# MesschieberV4.net
KiCad netlist of a schematic drawn in EAGLE
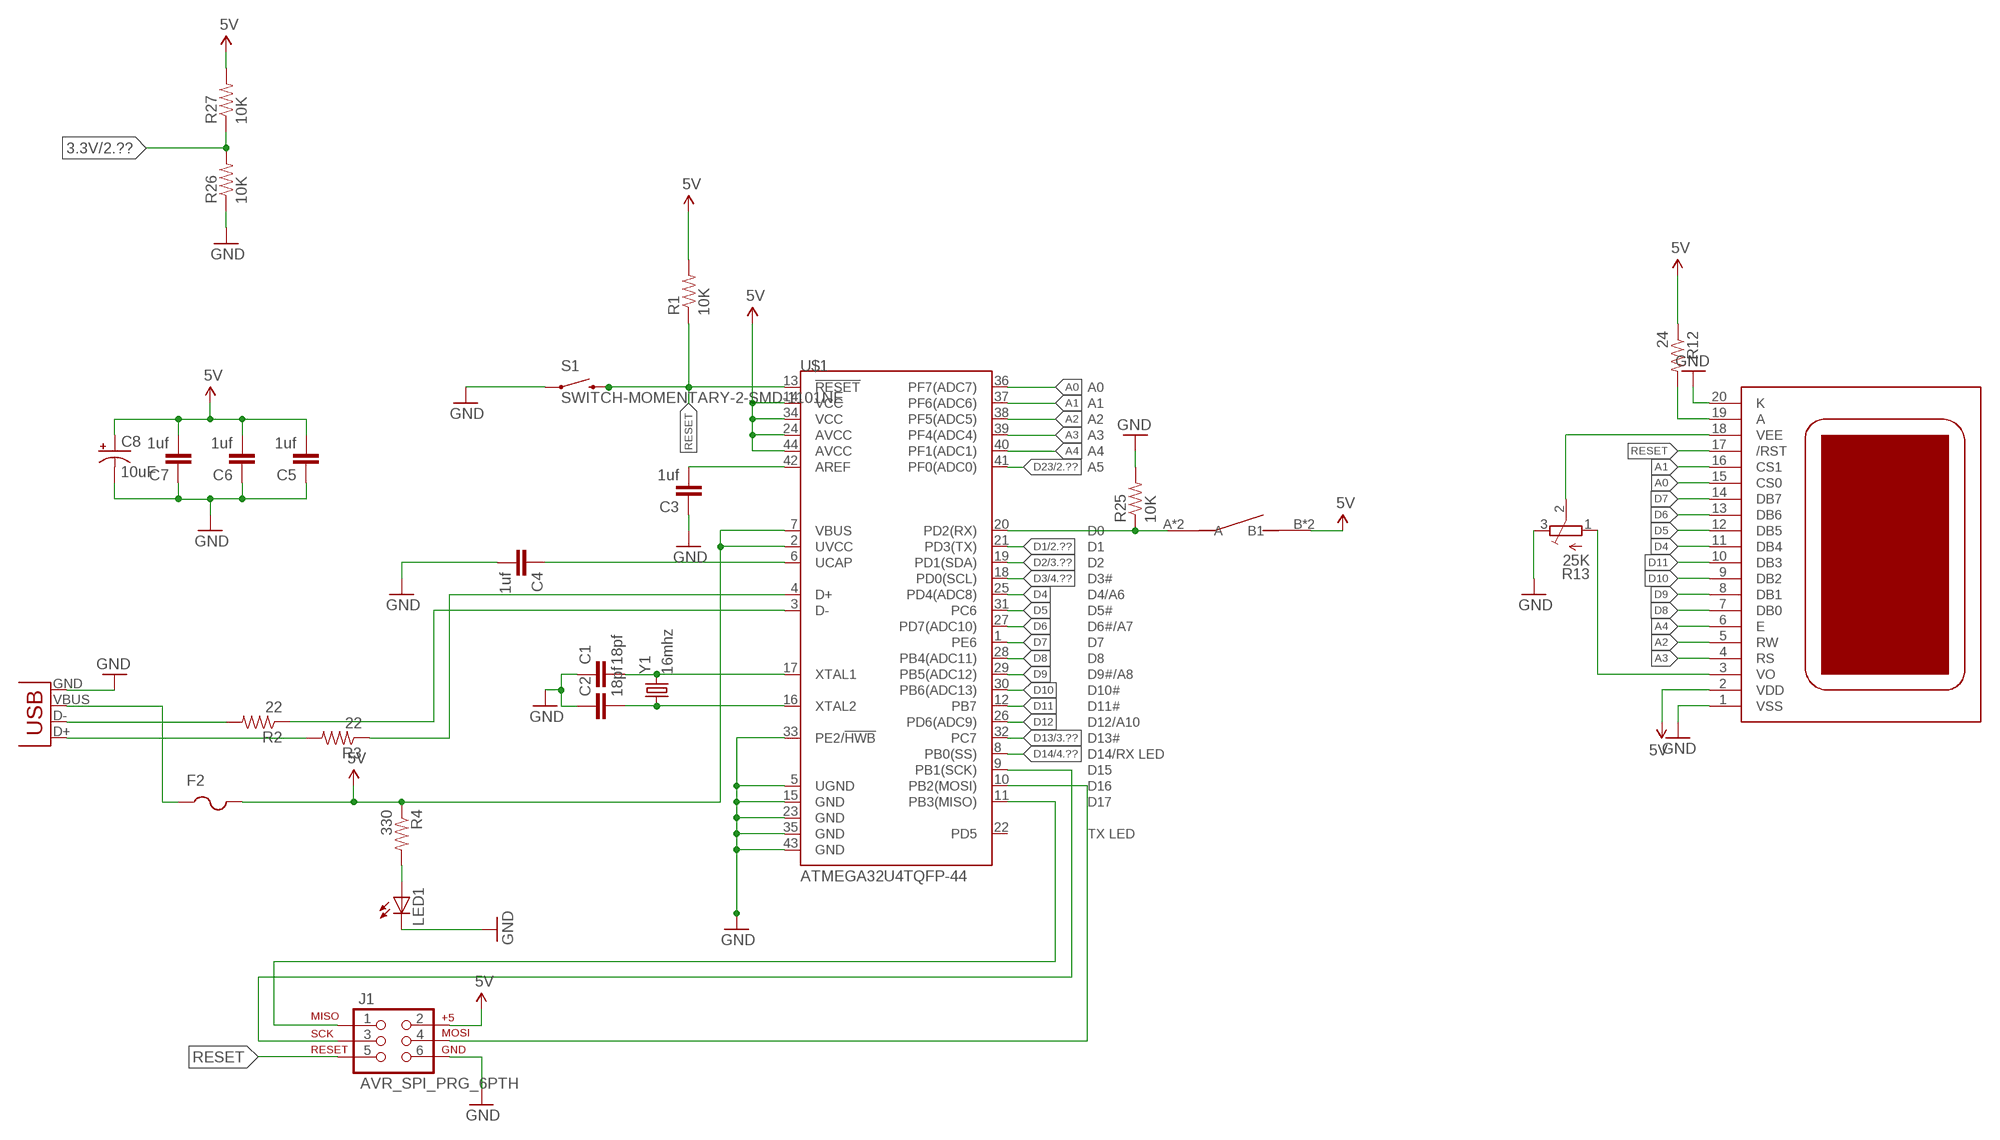
[diagram p0: schematic, sheet 1]
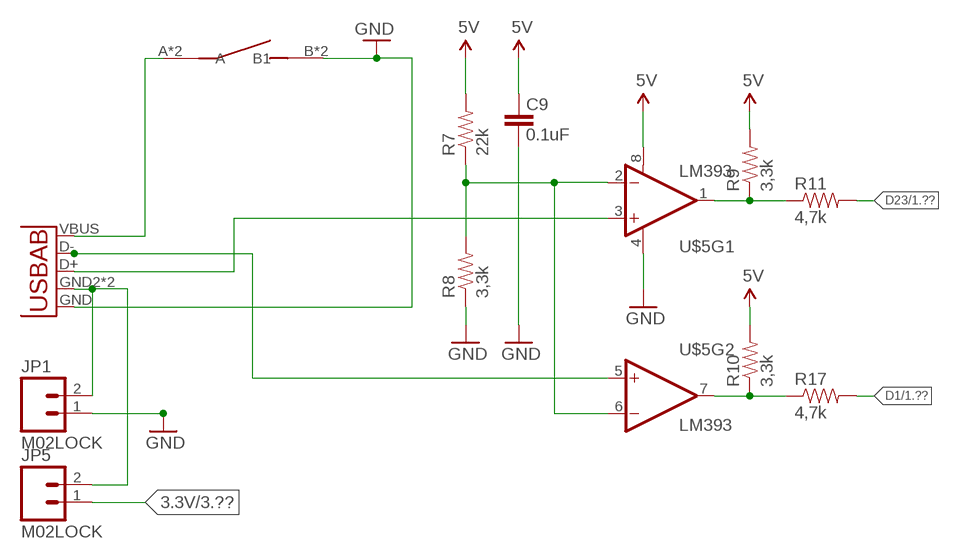
[diagram p1: schematic, sheet 2]
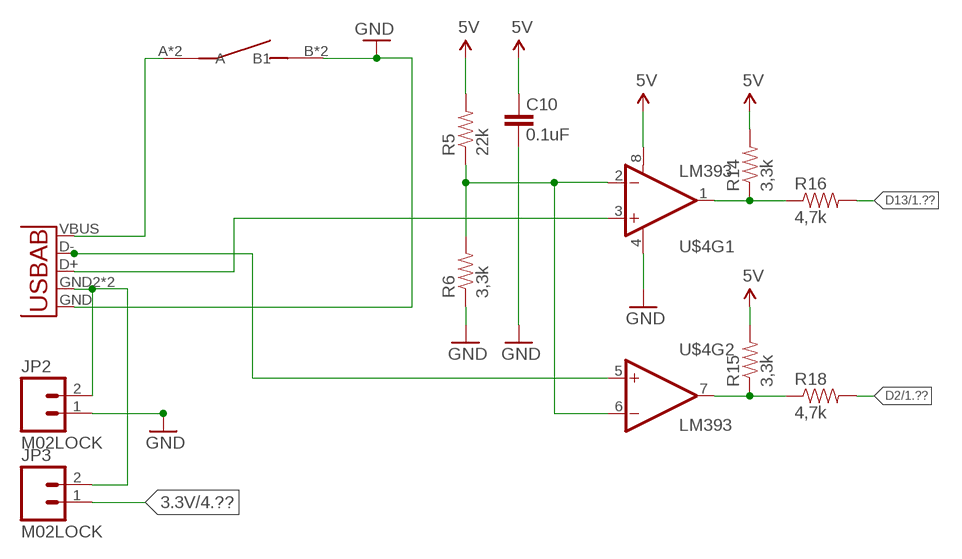
[diagram p2: schematic, sheet 3]
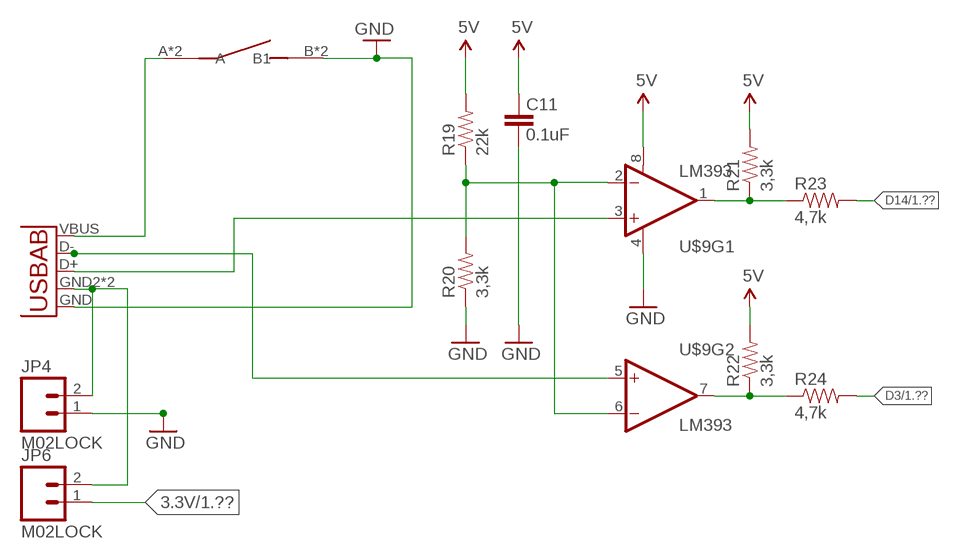
[diagram p3: schematic, sheet 4]

(export (version "E")
  (design (tool "Eeschema 10.0.6"))
  (components
    (comp (ref "C11")
      (value "0.1uF")
      (footprint "eagle-import:0805")
      (libsource (lib "eagle-import") (part "CAP0805"))
    )
    (comp (ref "JP4")
      (value "M02LOCK")
      (footprint "eagle-import:1X02_LOCK")
      (libsource (lib "eagle-import") (part "M02LOCK"))
    )
    (comp (ref "JP6")
      (value "M02LOCK")
      (footprint "eagle-import:1X02_LOCK")
      (libsource (lib "eagle-import") (part "M02LOCK"))
    )
    (comp (ref "R19")
      (value "22k")
      (footprint "eagle-import:0805")
      (libsource (lib "eagle-import") (part "RESISTOR"))
    )
    (comp (ref "R20")
      (value "3,3k")
      (footprint "eagle-import:0805")
      (libsource (lib "eagle-import") (part "RESISTOR"))
    )
    (comp (ref "R21")
      (value "3,3k")
      (footprint "eagle-import:0805")
      (libsource (lib "eagle-import") (part "RESISTOR"))
    )
    (comp (ref "R22")
      (value "3,3k")
      (footprint "eagle-import:0805")
      (libsource (lib "eagle-import") (part "RESISTOR"))
    )
    (comp (ref "R23")
      (value "4,7k")
      (footprint "eagle-import:0805")
      (libsource (lib "eagle-import") (part "RESISTOR"))
    )
    (comp (ref "R24")
      (value "4,7k")
      (footprint "eagle-import:0805")
      (libsource (lib "eagle-import") (part "RESISTOR"))
    )
    (comp (ref "U$9")
      (value "LM393")
      (footprint "eagle-import:SO08")
      (libsource (lib "eagle-import") (part "LM393"))
    )
    (comp (ref "U$10")
      (value "USB-A")
      (footprint "eagle-import:USB-A")
      (libsource (lib "eagle-import") (part "USB-A"))
    )
    (comp (ref "U$11")
      (value "TASTE_R3FTL6")
      (footprint "eagle-import:TASTE_R3FTL6")
      (libsource (lib "eagle-import") (part "TASTE_R3FTL6"))
    )
    (comp (ref "C10")
      (value "0.1uF")
      (footprint "eagle-import:0805")
      (libsource (lib "eagle-import") (part "CAP0805"))
    )
    (comp (ref "JP2")
      (value "M02LOCK")
      (footprint "eagle-import:1X02_LOCK")
      (libsource (lib "eagle-import") (part "M02LOCK"))
    )
    (comp (ref "JP3")
      (value "M02LOCK")
      (footprint "eagle-import:1X02_LOCK")
      (libsource (lib "eagle-import") (part "M02LOCK"))
    )
    (comp (ref "R5")
      (value "22k")
      (footprint "eagle-import:0805")
      (libsource (lib "eagle-import") (part "RESISTOR"))
    )
    (comp (ref "R6")
      (value "3,3k")
      (footprint "eagle-import:0805")
      (libsource (lib "eagle-import") (part "RESISTOR"))
    )
    (comp (ref "R14")
      (value "3,3k")
      (footprint "eagle-import:0805")
      (libsource (lib "eagle-import") (part "RESISTOR"))
    )
    (comp (ref "R15")
      (value "3,3k")
      (footprint "eagle-import:0805")
      (libsource (lib "eagle-import") (part "RESISTOR"))
    )
    (comp (ref "R16")
      (value "4,7k")
      (footprint "eagle-import:0805")
      (libsource (lib "eagle-import") (part "RESISTOR"))
    )
    (comp (ref "R18")
      (value "4,7k")
      (footprint "eagle-import:0805")
      (libsource (lib "eagle-import") (part "RESISTOR"))
    )
    (comp (ref "U$4")
      (value "LM393")
      (footprint "eagle-import:SO08")
      (libsource (lib "eagle-import") (part "LM393"))
    )
    (comp (ref "U$6")
      (value "USB-A")
      (footprint "eagle-import:USB-A")
      (libsource (lib "eagle-import") (part "USB-A"))
    )
    (comp (ref "U$8")
      (value "TASTE_R3FTL6")
      (footprint "eagle-import:TASTE_R3FTL6")
      (libsource (lib "eagle-import") (part "TASTE_R3FTL6"))
    )
    (comp (ref "C9")
      (value "0.1uF")
      (footprint "eagle-import:0805")
      (libsource (lib "eagle-import") (part "CAP0805"))
    )
    (comp (ref "JP1")
      (value "M02LOCK")
      (footprint "eagle-import:1X02_LOCK")
      (libsource (lib "eagle-import") (part "M02LOCK"))
    )
    (comp (ref "JP5")
      (value "M02LOCK")
      (footprint "eagle-import:1X02_LOCK")
      (libsource (lib "eagle-import") (part "M02LOCK"))
    )
    (comp (ref "R7")
      (value "22k")
      (footprint "eagle-import:0805")
      (libsource (lib "eagle-import") (part "RESISTOR"))
    )
    (comp (ref "R8")
      (value "3,3k")
      (footprint "eagle-import:0805")
      (libsource (lib "eagle-import") (part "RESISTOR"))
    )
    (comp (ref "R9")
      (value "3,3k")
      (footprint "eagle-import:0805")
      (libsource (lib "eagle-import") (part "RESISTOR"))
    )
    (comp (ref "R10")
      (value "3,3k")
      (footprint "eagle-import:0805")
      (libsource (lib "eagle-import") (part "RESISTOR"))
    )
    (comp (ref "R11")
      (value "4,7k")
      (footprint "eagle-import:0805")
      (libsource (lib "eagle-import") (part "RESISTOR"))
    )
    (comp (ref "R17")
      (value "4,7k")
      (footprint "eagle-import:0805")
      (libsource (lib "eagle-import") (part "RESISTOR"))
    )
    (comp (ref "U$3")
      (value "TASTE_R3FTL6")
      (footprint "eagle-import:TASTE_R3FTL6")
      (libsource (lib "eagle-import") (part "TASTE_R3FTL6"))
    )
    (comp (ref "U$5")
      (value "LM393")
      (footprint "eagle-import:SO08")
      (libsource (lib "eagle-import") (part "LM393"))
    )
    (comp (ref "U$7")
      (value "USB-A")
      (footprint "eagle-import:USB-A")
      (libsource (lib "eagle-import") (part "USB-A"))
    )
    (comp (ref "C1")
      (value "18pf")
      (footprint "eagle-import:0805")
      (libsource (lib "eagle-import") (part "SparkFun-Capacitors_CAP0805"))
    )
    (comp (ref "C2")
      (value "18pf")
      (footprint "eagle-import:0805")
      (libsource (lib "eagle-import") (part "SparkFun-Capacitors_CAP0805"))
    )
    (comp (ref "C3")
      (value "1uf")
      (footprint "eagle-import:0805")
      (libsource (lib "eagle-import") (part "SparkFun-Capacitors_CAP0805"))
    )
    (comp (ref "C4")
      (value "1uf")
      (footprint "eagle-import:0805")
      (libsource (lib "eagle-import") (part "SparkFun-Capacitors_CAP0805"))
    )
    (comp (ref "C5")
      (value "1uf")
      (footprint "eagle-import:0805")
      (libsource (lib "eagle-import") (part "SparkFun-Capacitors_CAP0805"))
    )
    (comp (ref "C6")
      (value "1uf")
      (footprint "eagle-import:0805")
      (libsource (lib "eagle-import") (part "SparkFun-Capacitors_CAP0805"))
    )
    (comp (ref "C7")
      (value "1uf")
      (footprint "eagle-import:0805")
      (libsource (lib "eagle-import") (part "SparkFun-Capacitors_CAP0805"))
    )
    (comp (ref "C8")
      (value "10uF")
      (footprint "eagle-import:EIA3528")
      (libsource (lib "eagle-import") (part "10UF-20V-10%(TANT)"))
    )
    (comp (ref "F2")
      (value "PTCFUSE-1812")
      (footprint "eagle-import:1812")
      (libsource (lib "eagle-import") (part "PTCFUSE-1812"))
    )
    (comp (ref "J1")
      (value "AVR_SPI_PRG_6PTH")
      (footprint "eagle-import:2X3")
      (libsource (lib "eagle-import") (part "AVR_SPI_PRG_6PTH"))
    )
    (comp (ref "JP7")
      (value "USB-SMD-NS")
      (footprint "eagle-import:USB-MINIB-NOSTOP")
      (libsource (lib "eagle-import") (part "USB-SMD-NS"))
    )
    (comp (ref "LED1")
      (value "LEDSML0805")
      (footprint "eagle-import:SML0805")
      (libsource (lib "eagle-import") (part "LEDSML0805"))
    )
    (comp (ref "R1")
      (value "10K")
      (footprint "eagle-import:0805")
      (libsource (lib "eagle-import") (part "RESISTOR"))
    )
    (comp (ref "R2")
      (value "22")
      (footprint "eagle-import:0805")
      (libsource (lib "eagle-import") (part "RESISTOR"))
    )
    (comp (ref "R3")
      (value "22")
      (footprint "eagle-import:0805")
      (libsource (lib "eagle-import") (part "RESISTOR"))
    )
    (comp (ref "R4")
      (value "330")
      (footprint "eagle-import:0805")
      (libsource (lib "eagle-import") (part "RESISTOR"))
    )
    (comp (ref "R12")
      (value "24")
      (footprint "eagle-import:0805")
      (libsource (lib "eagle-import") (part "RESISTOR"))
    )
    (comp (ref "R13")
      (value "25K")
      (footprint "eagle-import:SM-42_43A")
      (libsource (lib "eagle-import") (part "TRIM_EU-SM-42/43A"))
    )
    (comp (ref "R25")
      (value "10K")
      (footprint "eagle-import:0805")
      (libsource (lib "eagle-import") (part "RESISTOR"))
    )
    (comp (ref "R26")
      (value "10K")
      (footprint "eagle-import:0805")
      (libsource (lib "eagle-import") (part "RESISTOR"))
    )
    (comp (ref "R27")
      (value "10K")
      (footprint "eagle-import:0805")
      (libsource (lib "eagle-import") (part "RESISTOR"))
    )
    (comp (ref "S1")
      (value "SWITCH-MOMENTARY-2-SMD-1101NE")
      (footprint "eagle-import:TACTILE-SWITCH-1101NE")
      (libsource (lib "eagle-import") (part "SWITCH-MOMENTARY-2-SMD-1101NE"))
    )
    (comp (ref "U$1")
      (value "ATMEGA32U4TQFP-44")
      (footprint "eagle-import:TQFP44")
      (libsource (lib "eagle-import") (part "ATMEGA32U4TQFP-44"))
    )
    (comp (ref "U$2")
      (value "TS12864A")
      (footprint "eagle-import:TS12864")
      (libsource (lib "eagle-import") (part "TS12864A"))
    )
    (comp (ref "U$12")
      (value "TASTE_R3FTL6")
      (footprint "eagle-import:TASTE_R3FTL6")
      (libsource (lib "eagle-import") (part "TASTE_R3FTL6"))
    )
    (comp (ref "Y1")
      (value "16mhz")
      (footprint "eagle-import:CRYSTAL-SMD-5X3")
      (libsource (lib "eagle-import") (part "CRYSTAL5X3"))
    )
  )
  (nets
    (net (code "1") (name "3.3V") (class "Default")
      (node (ref "JP3") (pin "1") (pinfunction "1_1") (pintype "passive"))
      (node (ref "JP5") (pin "1") (pinfunction "1_1") (pintype "passive"))
      (node (ref "JP6") (pin "1") (pinfunction "1_1") (pintype "passive"))
      (node (ref "R26") (pin "2") (pinfunction "2_2") (pintype "passive"))
      (node (ref "R27") (pin "1") (pinfunction "1_1") (pintype "passive"))
    )
    (net (code "2") (name "5V") (class "Default")
      (node (ref "C10") (pin "2") (pinfunction "2_2") (pintype "passive"))
      (node (ref "C11") (pin "2") (pinfunction "2_2") (pintype "passive"))
      (node (ref "C5") (pin "2") (pinfunction "2_2") (pintype "passive"))
      (node (ref "C6") (pin "2") (pinfunction "2_2") (pintype "passive"))
      (node (ref "C7") (pin "2") (pinfunction "2_2") (pintype "passive"))
      (node (ref "C8") (pin "A") (pinfunction "+_A") (pintype "passive"))
      (node (ref "C9") (pin "2") (pinfunction "2_2") (pintype "passive"))
      (node (ref "F2") (pin "2") (pinfunction "2_2") (pintype "passive"))
      (node (ref "J1") (pin "2") (pinfunction "2_2") (pintype "passive"))
      (node (ref "R1") (pin "2") (pinfunction "2_2") (pintype "passive"))
      (node (ref "R10") (pin "2") (pinfunction "2_2") (pintype "passive"))
      (node (ref "R12") (pin "1") (pinfunction "1_1") (pintype "passive"))
      (node (ref "R14") (pin "2") (pinfunction "2_2") (pintype "passive"))
      (node (ref "R15") (pin "2") (pinfunction "2_2") (pintype "passive"))
      (node (ref "R19") (pin "2") (pinfunction "2_2") (pintype "passive"))
      (node (ref "R21") (pin "2") (pinfunction "2_2") (pintype "passive"))
      (node (ref "R22") (pin "2") (pinfunction "2_2") (pintype "passive"))
      (node (ref "R27") (pin "2") (pinfunction "2_2") (pintype "passive"))
      (node (ref "R4") (pin "1") (pinfunction "1_1") (pintype "passive"))
      (node (ref "R5") (pin "2") (pinfunction "2_2") (pintype "passive"))
      (node (ref "R7") (pin "2") (pinfunction "2_2") (pintype "passive"))
      (node (ref "R9") (pin "2") (pinfunction "2_2") (pintype "passive"))
      (node (ref "U$1") (pin "14") (pinfunction "VCC_14") (pintype "bidirectional"))
      (node (ref "U$1") (pin "2") (pinfunction "UVCC_2") (pintype "bidirectional"))
      (node (ref "U$1") (pin "24") (pinfunction "AVCC_24") (pintype "bidirectional"))
      (node (ref "U$1") (pin "34") (pinfunction "VCC_34") (pintype "bidirectional"))
      (node (ref "U$1") (pin "44") (pinfunction "AVCC_44") (pintype "bidirectional"))
      (node (ref "U$1") (pin "7") (pinfunction "VBUS_7") (pintype "bidirectional"))
      (node (ref "U$12") (pin "B") (pinfunction "B1_B") (pintype "bidirectional"))
      (node (ref "U$12") (pin "B1") (pinfunction "B1_B1") (pintype "bidirectional"))
      (node (ref "U$2") (pin "2") (pinfunction "VDD_2") (pintype "power_in"))
      (node (ref "U$4") (pin "8") (pinfunction "V+_8") (pintype "power_in"))
      (node (ref "U$5") (pin "8") (pinfunction "V+_8") (pintype "power_in"))
      (node (ref "U$9") (pin "8") (pinfunction "V+_8") (pintype "power_in"))
    )
    (net (code "3") (name "A0") (class "Default")
      (node (ref "U$1") (pin "36") (pinfunction "PF7(ADC7)_36") (pintype "bidirectional"))
      (node (ref "U$2") (pin "15") (pinfunction "CS0_15") (pintype "input"))
    )
    (net (code "4") (name "A1") (class "Default")
      (node (ref "U$1") (pin "37") (pinfunction "PF6(ADC6)_37") (pintype "bidirectional"))
      (node (ref "U$2") (pin "16") (pinfunction "CS1_16") (pintype "input"))
    )
    (net (code "5") (name "A2") (class "Default")
      (node (ref "U$1") (pin "38") (pinfunction "PF5(ADC5)_38") (pintype "bidirectional"))
      (node (ref "U$2") (pin "5") (pinfunction "RW_5") (pintype "input"))
    )
    (net (code "6") (name "A3") (class "Default")
      (node (ref "U$1") (pin "39") (pinfunction "PF4(ADC4)_39") (pintype "bidirectional"))
      (node (ref "U$2") (pin "4") (pinfunction "RS_4") (pintype "input"))
    )
    (net (code "7") (name "A4") (class "Default")
      (node (ref "U$1") (pin "40") (pinfunction "PF1(ADC1)_40") (pintype "bidirectional"))
      (node (ref "U$2") (pin "6") (pinfunction "E_6") (pintype "input"))
    )
    (net (code "8") (name "D1") (class "Default")
      (node (ref "R17") (pin "2") (pinfunction "2_2") (pintype "passive"))
      (node (ref "U$1") (pin "21") (pinfunction "PD3(TX)_21") (pintype "bidirectional"))
    )
    (net (code "9") (name "D2") (class "Default")
      (node (ref "R18") (pin "2") (pinfunction "2_2") (pintype "passive"))
      (node (ref "U$1") (pin "19") (pinfunction "PD1(SDA)_19") (pintype "bidirectional"))
    )
    (net (code "10") (name "D3") (class "Default")
      (node (ref "R24") (pin "2") (pinfunction "2_2") (pintype "passive"))
      (node (ref "U$1") (pin "18") (pinfunction "PD0(SCL)_18") (pintype "bidirectional"))
    )
    (net (code "11") (name "D4") (class "Default")
      (node (ref "U$1") (pin "25") (pinfunction "PD4(ADC8)_25") (pintype "bidirectional"))
      (node (ref "U$2") (pin "11") (pinfunction "DB4_11") (pintype "bidirectional"))
    )
    (net (code "12") (name "D5") (class "Default")
      (node (ref "U$1") (pin "31") (pinfunction "PC6_31") (pintype "bidirectional"))
      (node (ref "U$2") (pin "12") (pinfunction "DB5_12") (pintype "bidirectional"))
    )
    (net (code "13") (name "D6") (class "Default")
      (node (ref "U$1") (pin "27") (pinfunction "PD7(ADC10)_27") (pintype "bidirectional"))
      (node (ref "U$2") (pin "13") (pinfunction "DB6_13") (pintype "bidirectional"))
    )
    (net (code "14") (name "D7") (class "Default")
      (node (ref "U$1") (pin "1") (pinfunction "PE6_1") (pintype "bidirectional"))
      (node (ref "U$2") (pin "14") (pinfunction "DB7_14") (pintype "bidirectional"))
    )
    (net (code "15") (name "D8") (class "Default")
      (node (ref "U$1") (pin "28") (pinfunction "PB4(ADC11)_28") (pintype "bidirectional"))
      (node (ref "U$2") (pin "7") (pinfunction "DB0_7") (pintype "bidirectional"))
    )
    (net (code "16") (name "D9") (class "Default")
      (node (ref "U$1") (pin "29") (pinfunction "PB5(ADC12)_29") (pintype "bidirectional"))
      (node (ref "U$2") (pin "8") (pinfunction "DB1_8") (pintype "bidirectional"))
    )
    (net (code "17") (name "D10") (class "Default")
      (node (ref "U$1") (pin "30") (pinfunction "PB6(ADC13)_30") (pintype "bidirectional"))
      (node (ref "U$2") (pin "9") (pinfunction "DB2_9") (pintype "bidirectional"))
    )
    (net (code "18") (name "D11") (class "Default")
      (node (ref "U$1") (pin "12") (pinfunction "PB7_12") (pintype "bidirectional"))
      (node (ref "U$2") (pin "10") (pinfunction "DB3_10") (pintype "bidirectional"))
    )
    (net (code "19") (name "D12") (class "Default")
      (node (ref "U$1") (pin "26") (pinfunction "PD6(ADC9)_26") (pintype "bidirectional"))
    )
    (net (code "20") (name "D13") (class "Default")
      (node (ref "R16") (pin "2") (pinfunction "2_2") (pintype "passive"))
      (node (ref "U$1") (pin "32") (pinfunction "PC7_32") (pintype "bidirectional"))
    )
    (net (code "21") (name "D14") (class "Default")
      (node (ref "R23") (pin "2") (pinfunction "2_2") (pintype "passive"))
      (node (ref "U$1") (pin "8") (pinfunction "PB0(SS)_8") (pintype "bidirectional"))
    )
    (net (code "22") (name "D23") (class "Default")
      (node (ref "R11") (pin "2") (pinfunction "2_2") (pintype "passive"))
      (node (ref "U$1") (pin "41") (pinfunction "PF0(ADC0)_41") (pintype "bidirectional"))
    )
    (net (code "23") (name "GND") (class "Default")
      (node (ref "C1") (pin "1") (pinfunction "1_1") (pintype "passive"))
      (node (ref "C10") (pin "1") (pinfunction "1_1") (pintype "passive"))
      (node (ref "C11") (pin "1") (pinfunction "1_1") (pintype "passive"))
      (node (ref "C2") (pin "1") (pinfunction "1_1") (pintype "passive"))
      (node (ref "C3") (pin "1") (pinfunction "1_1") (pintype "passive"))
      (node (ref "C4") (pin "2") (pinfunction "2_2") (pintype "passive"))
      (node (ref "C5") (pin "1") (pinfunction "1_1") (pintype "passive"))
      (node (ref "C6") (pin "1") (pinfunction "1_1") (pintype "passive"))
      (node (ref "C7") (pin "1") (pinfunction "1_1") (pintype "passive"))
      (node (ref "C8") (pin "C") (pinfunction "-_C") (pintype "passive"))
      (node (ref "C9") (pin "1") (pinfunction "1_1") (pintype "passive"))
      (node (ref "J1") (pin "6") (pinfunction "6_6") (pintype "passive"))
      (node (ref "JP1") (pin "1") (pinfunction "1_1") (pintype "passive"))
      (node (ref "JP2") (pin "1") (pinfunction "1_1") (pintype "passive"))
      (node (ref "JP4") (pin "1") (pinfunction "1_1") (pintype "passive"))
      (node (ref "JP7") (pin "GND") (pinfunction "GND_GND") (pintype "bidirectional"))
      (node (ref "LED1") (pin "C") (pinfunction "C_C") (pintype "passive"))
      (node (ref "R13") (pin "3") (pinfunction "E_3") (pintype "passive"))
      (node (ref "R20") (pin "1") (pinfunction "1_1") (pintype "passive"))
      (node (ref "R25") (pin "2") (pinfunction "2_2") (pintype "passive"))
      (node (ref "R26") (pin "1") (pinfunction "1_1") (pintype "passive"))
      (node (ref "R6") (pin "1") (pinfunction "1_1") (pintype "passive"))
      (node (ref "R8") (pin "1") (pinfunction "1_1") (pintype "passive"))
      (node (ref "S1") (pin "P$1") (pinfunction "1_P$1") (pintype "passive"))
      (node (ref "U$1") (pin "15") (pinfunction "GND_15") (pintype "bidirectional"))
      (node (ref "U$1") (pin "23") (pinfunction "GND_23") (pintype "bidirectional"))
      (node (ref "U$1") (pin "33") (pinfunction "PE2/~{HWB}_33") (pintype "bidirectional"))
      (node (ref "U$1") (pin "35") (pinfunction "GND_35") (pintype "bidirectional"))
      (node (ref "U$1") (pin "43") (pinfunction "GND_43") (pintype "bidirectional"))
      (node (ref "U$1") (pin "5") (pinfunction "UGND_5") (pintype "bidirectional"))
      (node (ref "U$10") (pin "GND") (pinfunction "GND_GND") (pintype "bidirectional"))
      (node (ref "U$11") (pin "B") (pinfunction "B1_B") (pintype "bidirectional"))
      (node (ref "U$11") (pin "B1") (pinfunction "B1_B1") (pintype "bidirectional"))
      (node (ref "U$2") (pin "1") (pinfunction "VSS_1") (pintype "power_in"))
      (node (ref "U$2") (pin "20") (pinfunction "K_20") (pintype "input"))
      (node (ref "U$3") (pin "B") (pinfunction "B1_B") (pintype "bidirectional"))
      (node (ref "U$3") (pin "B1") (pinfunction "B1_B1") (pintype "bidirectional"))
      (node (ref "U$4") (pin "4") (pinfunction "V-_4") (pintype "power_in"))
      (node (ref "U$5") (pin "4") (pinfunction "V-_4") (pintype "power_in"))
      (node (ref "U$6") (pin "GND") (pinfunction "GND_GND") (pintype "bidirectional"))
      (node (ref "U$7") (pin "GND") (pinfunction "GND_GND") (pintype "bidirectional"))
      (node (ref "U$8") (pin "B") (pinfunction "B1_B") (pintype "bidirectional"))
      (node (ref "U$8") (pin "B1") (pinfunction "B1_B1") (pintype "bidirectional"))
      (node (ref "U$9") (pin "4") (pinfunction "V-_4") (pintype "power_in"))
    )
    (net (code "24") (name "Net-(F2-Pad1)") (class "Default")
      (node (ref "F2") (pin "1") (pinfunction "1_1") (pintype "passive"))
      (node (ref "JP7") (pin "VBUS") (pinfunction "VBUS_VBUS") (pintype "bidirectional"))
    )
    (net (code "25") (name "Net-(JP1-Pad2)") (class "Default")
      (node (ref "JP1") (pin "2") (pinfunction "2_2") (pintype "passive"))
      (node (ref "JP5") (pin "2") (pinfunction "2_2") (pintype "passive"))
      (node (ref "U$7") (pin "GND2") (pinfunction "USBID_GND2") (pintype "bidirectional"))
      (node (ref "U$7") (pin "GND3") (pinfunction "USBID_GND3") (pintype "bidirectional"))
    )
    (net (code "26") (name "Net-(JP2-Pad2)") (class "Default")
      (node (ref "JP2") (pin "2") (pinfunction "2_2") (pintype "passive"))
      (node (ref "JP3") (pin "2") (pinfunction "2_2") (pintype "passive"))
      (node (ref "U$6") (pin "GND2") (pinfunction "USBID_GND2") (pintype "bidirectional"))
      (node (ref "U$6") (pin "GND3") (pinfunction "USBID_GND3") (pintype "bidirectional"))
    )
    (net (code "27") (name "Net-(JP4-Pad2)") (class "Default")
      (node (ref "JP4") (pin "2") (pinfunction "2_2") (pintype "passive"))
      (node (ref "JP6") (pin "2") (pinfunction "2_2") (pintype "passive"))
      (node (ref "U$10") (pin "GND2") (pinfunction "USBID_GND2") (pintype "bidirectional"))
      (node (ref "U$10") (pin "GND3") (pinfunction "USBID_GND3") (pintype "bidirectional"))
    )
    (net (code "28") (name "Net-(JP7-PadD+)") (class "Default")
      (node (ref "JP7") (pin "D+") (pinfunction "D+_D+") (pintype "bidirectional"))
      (node (ref "R3") (pin "2") (pinfunction "2_2") (pintype "passive"))
    )
    (net (code "29") (name "Net-(JP7-PadD-)") (class "Default")
      (node (ref "JP7") (pin "D-") (pinfunction "D-_D-") (pintype "bidirectional"))
      (node (ref "R2") (pin "2") (pinfunction "2_2") (pintype "passive"))
    )
    (net (code "30") (name "Net-(LED1-PadA)") (class "Default")
      (node (ref "LED1") (pin "A") (pinfunction "A_A") (pintype "passive"))
      (node (ref "R4") (pin "2") (pinfunction "2_2") (pintype "passive"))
    )
    (net (code "31") (name "Net-(R13-A)") (class "Default")
      (node (ref "R13") (pin "1") (pinfunction "A_1") (pintype "passive"))
      (node (ref "U$2") (pin "3") (pinfunction "VO_3") (pintype "input"))
    )
    (net (code "32") (name "Net-(R13-S)") (class "Default")
      (node (ref "R13") (pin "2") (pinfunction "S_2") (pintype "passive"))
      (node (ref "U$2") (pin "18") (pinfunction "VEE_18") (pintype "power_in"))
    )
    (net (code "33") (name "Net-(U$1-AREF)") (class "Default")
      (node (ref "C3") (pin "2") (pinfunction "2_2") (pintype "passive"))
      (node (ref "U$1") (pin "42") (pinfunction "AREF_42") (pintype "bidirectional"))
    )
    (net (code "34") (name "Net-(U$1-D+)") (class "Default")
      (node (ref "R3") (pin "1") (pinfunction "1_1") (pintype "passive"))
      (node (ref "U$1") (pin "4") (pinfunction "D+_4") (pintype "bidirectional"))
    )
    (net (code "35") (name "Net-(U$1-D-)") (class "Default")
      (node (ref "R2") (pin "1") (pinfunction "1_1") (pintype "passive"))
      (node (ref "U$1") (pin "3") (pinfunction "D-_3") (pintype "bidirectional"))
    )
    (net (code "36") (name "Net-(U$1-PB1(SCK))") (class "Default")
      (node (ref "J1") (pin "3") (pinfunction "3_3") (pintype "passive"))
      (node (ref "U$1") (pin "9") (pinfunction "PB1(SCK)_9") (pintype "bidirectional"))
    )
    (net (code "37") (name "Net-(U$1-PB2(MOSI))") (class "Default")
      (node (ref "J1") (pin "4") (pinfunction "4_4") (pintype "passive"))
      (node (ref "U$1") (pin "10") (pinfunction "PB2(MOSI)_10") (pintype "bidirectional"))
    )
    (net (code "38") (name "Net-(U$1-PB3(MISO))") (class "Default")
      (node (ref "J1") (pin "1") (pinfunction "1_1") (pintype "passive"))
      (node (ref "U$1") (pin "11") (pinfunction "PB3(MISO)_11") (pintype "bidirectional"))
    )
    (net (code "39") (name "Net-(U$1-PD2(RX))") (class "Default")
      (node (ref "R25") (pin "1") (pinfunction "1_1") (pintype "passive"))
      (node (ref "U$1") (pin "20") (pinfunction "PD2(RX)_20") (pintype "bidirectional"))
      (node (ref "U$12") (pin "A") (pinfunction "A_A") (pintype "bidirectional"))
      (node (ref "U$12") (pin "A1") (pinfunction "A_A1") (pintype "bidirectional"))
    )
    (net (code "40") (name "Net-(U$1-UCAP)") (class "Default")
      (node (ref "C4") (pin "1") (pinfunction "1_1") (pintype "passive"))
      (node (ref "U$1") (pin "6") (pinfunction "UCAP_6") (pintype "bidirectional"))
    )
    (net (code "41") (name "Net-(U$1-XTAL1)") (class "Default")
      (node (ref "C1") (pin "2") (pinfunction "2_2") (pintype "passive"))
      (node (ref "U$1") (pin "17") (pinfunction "XTAL1_17") (pintype "bidirectional"))
      (node (ref "Y1") (pin "3") (pinfunction "2_3") (pintype "passive"))
    )
    (net (code "42") (name "Net-(U$1-XTAL2)") (class "Default")
      (node (ref "C2") (pin "2") (pinfunction "2_2") (pintype "passive"))
      (node (ref "U$1") (pin "16") (pinfunction "XTAL2_16") (pintype "bidirectional"))
      (node (ref "Y1") (pin "1") (pinfunction "1_1") (pintype "passive"))
    )
    (net (code "43") (name "Net-(U$2-A)") (class "Default")
      (node (ref "R12") (pin "2") (pinfunction "2_2") (pintype "passive"))
      (node (ref "U$2") (pin "19") (pinfunction "A_19") (pintype "power_in"))
    )
    (net (code "44") (name "Net-(U$3-A-PadA1)") (class "Default")
      (node (ref "U$3") (pin "A") (pinfunction "A_A") (pintype "bidirectional"))
      (node (ref "U$3") (pin "A1") (pinfunction "A_A1") (pintype "bidirectional"))
      (node (ref "U$7") (pin "VBUS") (pinfunction "VBUS_VBUS") (pintype "bidirectional"))
    )
    (net (code "45") (name "Net-(U$4A-+IN)") (class "Default")
      (node (ref "U$4") (pin "3") (pinfunction "+IN_3") (pintype "input"))
      (node (ref "U$6") (pin "D+") (pinfunction "D+_D+") (pintype "bidirectional"))
    )
    (net (code "46") (name "Net-(U$4A--IN)") (class "Default")
      (node (ref "R5") (pin "1") (pinfunction "1_1") (pintype "passive"))
      (node (ref "R6") (pin "2") (pinfunction "2_2") (pintype "passive"))
      (node (ref "U$4") (pin "2") (pinfunction "-IN_2") (pintype "input"))
      (node (ref "U$4") (pin "6") (pinfunction "-IN_6") (pintype "input"))
    )
    (net (code "47") (name "Net-(U$4A-OUT)") (class "Default")
      (node (ref "R14") (pin "1") (pinfunction "1_1") (pintype "passive"))
      (node (ref "R16") (pin "1") (pinfunction "1_1") (pintype "passive"))
      (node (ref "U$4") (pin "1") (pinfunction "OUT_1") (pintype "output"))
    )
    (net (code "48") (name "Net-(U$4B-+IN)") (class "Default")
      (node (ref "U$4") (pin "5") (pinfunction "+IN_5") (pintype "input"))
      (node (ref "U$6") (pin "D-") (pinfunction "D-_D-") (pintype "bidirectional"))
    )
    (net (code "49") (name "Net-(U$4B-OUT)") (class "Default")
      (node (ref "R15") (pin "1") (pinfunction "1_1") (pintype "passive"))
      (node (ref "R18") (pin "1") (pinfunction "1_1") (pintype "passive"))
      (node (ref "U$4") (pin "7") (pinfunction "OUT_7") (pintype "output"))
    )
    (net (code "50") (name "Net-(U$5A-+IN)") (class "Default")
      (node (ref "U$5") (pin "3") (pinfunction "+IN_3") (pintype "input"))
      (node (ref "U$7") (pin "D+") (pinfunction "D+_D+") (pintype "bidirectional"))
    )
    (net (code "51") (name "Net-(U$5A--IN)") (class "Default")
      (node (ref "R7") (pin "1") (pinfunction "1_1") (pintype "passive"))
      (node (ref "R8") (pin "2") (pinfunction "2_2") (pintype "passive"))
      (node (ref "U$5") (pin "2") (pinfunction "-IN_2") (pintype "input"))
      (node (ref "U$5") (pin "6") (pinfunction "-IN_6") (pintype "input"))
    )
    (net (code "52") (name "Net-(U$5A-OUT)") (class "Default")
      (node (ref "R11") (pin "1") (pinfunction "1_1") (pintype "passive"))
      (node (ref "R9") (pin "1") (pinfunction "1_1") (pintype "passive"))
      (node (ref "U$5") (pin "1") (pinfunction "OUT_1") (pintype "output"))
    )
    (net (code "53") (name "Net-(U$5B-+IN)") (class "Default")
      (node (ref "U$5") (pin "5") (pinfunction "+IN_5") (pintype "input"))
      (node (ref "U$7") (pin "D-") (pinfunction "D-_D-") (pintype "bidirectional"))
    )
    (net (code "54") (name "Net-(U$5B-OUT)") (class "Default")
      (node (ref "R10") (pin "1") (pinfunction "1_1") (pintype "passive"))
      (node (ref "R17") (pin "1") (pinfunction "1_1") (pintype "passive"))
      (node (ref "U$5") (pin "7") (pinfunction "OUT_7") (pintype "output"))
    )
    (net (code "55") (name "Net-(U$6-PadVBUS)") (class "Default")
      (node (ref "U$6") (pin "VBUS") (pinfunction "VBUS_VBUS") (pintype "bidirectional"))
      (node (ref "U$8") (pin "A") (pinfunction "A_A") (pintype "bidirectional"))
      (node (ref "U$8") (pin "A1") (pinfunction "A_A1") (pintype "bidirectional"))
    )
    (net (code "56") (name "Net-(U$9A-+IN)") (class "Default")
      (node (ref "U$10") (pin "D+") (pinfunction "D+_D+") (pintype "bidirectional"))
      (node (ref "U$9") (pin "3") (pinfunction "+IN_3") (pintype "input"))
    )
    (net (code "57") (name "Net-(U$9A--IN)") (class "Default")
      (node (ref "R19") (pin "1") (pinfunction "1_1") (pintype "passive"))
      (node (ref "R20") (pin "2") (pinfunction "2_2") (pintype "passive"))
      (node (ref "U$9") (pin "2") (pinfunction "-IN_2") (pintype "input"))
      (node (ref "U$9") (pin "6") (pinfunction "-IN_6") (pintype "input"))
    )
    (net (code "58") (name "Net-(U$9A-OUT)") (class "Default")
      (node (ref "R21") (pin "1") (pinfunction "1_1") (pintype "passive"))
      (node (ref "R23") (pin "1") (pinfunction "1_1") (pintype "passive"))
      (node (ref "U$9") (pin "1") (pinfunction "OUT_1") (pintype "output"))
    )
    (net (code "59") (name "Net-(U$9B-+IN)") (class "Default")
      (node (ref "U$10") (pin "D-") (pinfunction "D-_D-") (pintype "bidirectional"))
      (node (ref "U$9") (pin "5") (pinfunction "+IN_5") (pintype "input"))
    )
    (net (code "60") (name "Net-(U$9B-OUT)") (class "Default")
      (node (ref "R22") (pin "1") (pinfunction "1_1") (pintype "passive"))
      (node (ref "R24") (pin "1") (pinfunction "1_1") (pintype "passive"))
      (node (ref "U$9") (pin "7") (pinfunction "OUT_7") (pintype "output"))
    )
    (net (code "61") (name "Net-(U$10-PadVBUS)") (class "Default")
      (node (ref "U$10") (pin "VBUS") (pinfunction "VBUS_VBUS") (pintype "bidirectional"))
      (node (ref "U$11") (pin "A") (pinfunction "A_A") (pintype "bidirectional"))
      (node (ref "U$11") (pin "A1") (pinfunction "A_A1") (pintype "bidirectional"))
    )
    (net (code "62") (name "RESET") (class "Default")
      (node (ref "J1") (pin "5") (pinfunction "5_5") (pintype "passive"))
      (node (ref "R1") (pin "1") (pinfunction "1_1") (pintype "passive"))
      (node (ref "S1") (pin "P$2") (pinfunction "2_P$2") (pintype "passive"))
      (node (ref "U$1") (pin "13") (pinfunction "~{RESET}_13") (pintype "bidirectional"))
      (node (ref "U$2") (pin "17") (pinfunction "/RST_17") (pintype "input"))
    )
    (net (code "63") (name "unconnected-(U$1-PD5-Pad22)") (class "Default")
      (node (ref "U$1") (pin "22") (pinfunction "PD5_22") (pintype "bidirectional"))
    )
  )
)
